# MCU.net
KiCad netlist of a schematic drawn in Altium Designer
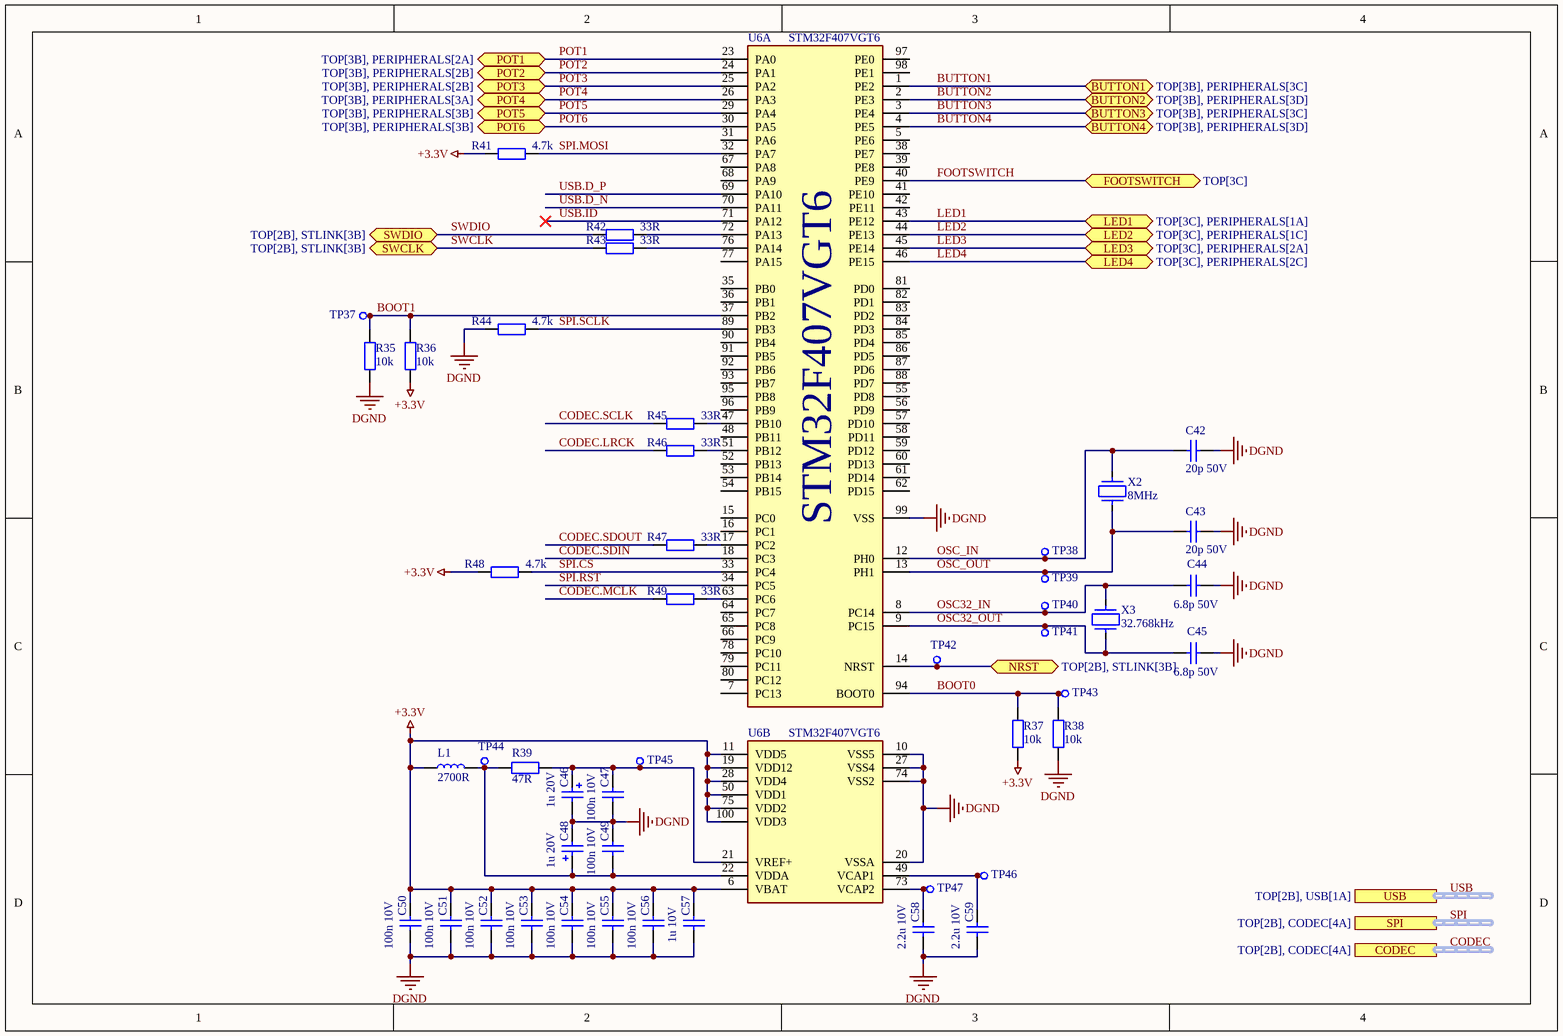
[diagram p0: MCU.SchDoc]

(export (version "E")
  (design (tool "Eeschema 10.0.6"))
  (components
    (comp (ref "C42")
      (value "20p 50V")
      (footprint "FOOTPRINTS:CAPACITOR 0805")
      (description "Capacitor: ceramic; MLCC; 20pF; 50V; C0G (NP0); ±5%; SMD; 0805")
      (fields
        (field (name "MANUFACTURER") "KYOCERA AVX")
        (field (name "MANUFACTURER PART NUMBER") "08055A200JAT2A")
      )
      (libsource (lib "SYMBOLS") (part "Capacitor 20p 50V ±5% NP0 0805"))
    )
    (comp (ref "C43")
      (value "20p 50V")
      (footprint "FOOTPRINTS:CAPACITOR 0805")
      (description "Capacitor: ceramic; MLCC; 20pF; 50V; C0G (NP0); ±5%; SMD; 0805")
      (fields
        (field (name "MANUFACTURER") "KYOCERA AVX")
        (field (name "MANUFACTURER PART NUMBER") "08055A200JAT2A")
      )
      (libsource (lib "SYMBOLS") (part "Capacitor 20p 50V ±5% NP0 0805"))
    )
    (comp (ref "C44")
      (value "6.8p 50V")
      (footprint "FOOTPRINTS:CAPACITOR 0805")
      (description "Capacitor: ceramic; MLCC; 6.8pF; 50V; C0G (NP0); ±0.25pF; SMD; 0805")
      (fields
        (field (name "MANUFACTURER") "YAGEO")
        (field (name "MANUFACTURER PART NUMBER") "CC0805CRNPO96R8")
      )
      (libsource (lib "SYMBOLS") (part "Capacitor 6.8p 50V ±0.25pF NP0 0805"))
    )
    (comp (ref "C45")
      (value "6.8p 50V")
      (footprint "FOOTPRINTS:CAPACITOR 0805")
      (description "Capacitor: ceramic; MLCC; 6.8pF; 50V; C0G (NP0); ±0.25pF; SMD; 0805")
      (fields
        (field (name "MANUFACTURER") "YAGEO")
        (field (name "MANUFACTURER PART NUMBER") "CC0805CRNPO96R8")
      )
      (libsource (lib "SYMBOLS") (part "Capacitor 6.8p 50V ±0.25pF NP0 0805"))
    )
    (comp (ref "C46")
      (value "1u 20V")
      (footprint "FOOTPRINTS:CAPACITOR 1206")
      (description "Capacitor: tantalum; 1uF; 20VDC; SMD; A; 1206; ±10%; -55÷125°C; T491")
      (fields
        (field (name "MANUFACTURER") "KEMET")
        (field (name "MANUFACTURER PART NUMBER") "T491A105K020AT")
      )
      (libsource (lib "SYMBOLS") (part "Capacitor 1u 20V 20% Tantalum 1206"))
    )
    (comp (ref "C47")
      (value "100n 10V")
      (footprint "FOOTPRINTS:CAPACITOR 0805")
      (description "Capacitor: ceramic; MLCC; 100nF; 100V; X7R; ±10%; SMD; 0805")
      (fields
        (field (name "MANUFACTURER") "YAGEO")
        (field (name "MANUFACTURER PART NUMBER") "CC0805KKX7R0BB104")
      )
      (libsource (lib "SYMBOLS") (part "Capacitor 100n 100V 10% X7R 0805"))
    )
    (comp (ref "C48")
      (value "1u 20V")
      (footprint "FOOTPRINTS:CAPACITOR 1206")
      (description "Capacitor: tantalum; 1uF; 20VDC; SMD; A; 1206; ±10%; -55÷125°C; T491")
      (fields
        (field (name "MANUFACTURER") "KEMET")
        (field (name "MANUFACTURER PART NUMBER") "T491A105K020AT")
      )
      (libsource (lib "SYMBOLS") (part "Capacitor 1u 20V 20% Tantalum 1206"))
    )
    (comp (ref "C49")
      (value "100n 10V")
      (footprint "FOOTPRINTS:CAPACITOR 0805")
      (description "Capacitor: ceramic; MLCC; 100nF; 100V; X7R; ±10%; SMD; 0805")
      (fields
        (field (name "MANUFACTURER") "YAGEO")
        (field (name "MANUFACTURER PART NUMBER") "CC0805KKX7R0BB104")
      )
      (libsource (lib "SYMBOLS") (part "Capacitor 100n 100V 10% X7R 0805"))
    )
    (comp (ref "C50")
      (value "100n 10V")
      (footprint "FOOTPRINTS:CAPACITOR 0805")
      (description "Capacitor: ceramic; MLCC; 100nF; 100V; X7R; ±10%; SMD; 0805")
      (fields
        (field (name "MANUFACTURER") "YAGEO")
        (field (name "MANUFACTURER PART NUMBER") "CC0805KKX7R0BB104")
      )
      (libsource (lib "SYMBOLS") (part "Capacitor 100n 100V 10% X7R 0805"))
    )
    (comp (ref "C51")
      (value "100n 10V")
      (footprint "FOOTPRINTS:CAPACITOR 0805")
      (description "Capacitor: ceramic; MLCC; 100nF; 100V; X7R; ±10%; SMD; 0805")
      (fields
        (field (name "MANUFACTURER") "YAGEO")
        (field (name "MANUFACTURER PART NUMBER") "CC0805KKX7R0BB104")
      )
      (libsource (lib "SYMBOLS") (part "Capacitor 100n 100V 10% X7R 0805"))
    )
    (comp (ref "C52")
      (value "100n 10V")
      (footprint "FOOTPRINTS:CAPACITOR 0805")
      (description "Capacitor: ceramic; MLCC; 100nF; 100V; X7R; ±10%; SMD; 0805")
      (fields
        (field (name "MANUFACTURER") "YAGEO")
        (field (name "MANUFACTURER PART NUMBER") "CC0805KKX7R0BB104")
      )
      (libsource (lib "SYMBOLS") (part "Capacitor 100n 100V 10% X7R 0805"))
    )
    (comp (ref "C53")
      (value "100n 10V")
      (footprint "FOOTPRINTS:CAPACITOR 0805")
      (description "Capacitor: ceramic; MLCC; 100nF; 100V; X7R; ±10%; SMD; 0805")
      (fields
        (field (name "MANUFACTURER") "YAGEO")
        (field (name "MANUFACTURER PART NUMBER") "CC0805KKX7R0BB104")
      )
      (libsource (lib "SYMBOLS") (part "Capacitor 100n 100V 10% X7R 0805"))
    )
    (comp (ref "C54")
      (value "100n 10V")
      (footprint "FOOTPRINTS:CAPACITOR 0805")
      (description "Capacitor: ceramic; MLCC; 100nF; 100V; X7R; ±10%; SMD; 0805")
      (fields
        (field (name "MANUFACTURER") "YAGEO")
        (field (name "MANUFACTURER PART NUMBER") "CC0805KKX7R0BB104")
      )
      (libsource (lib "SYMBOLS") (part "Capacitor 100n 100V 10% X7R 0805"))
    )
    (comp (ref "C55")
      (value "100n 10V")
      (footprint "FOOTPRINTS:CAPACITOR 0805")
      (description "Capacitor: ceramic; MLCC; 100nF; 100V; X7R; ±10%; SMD; 0805")
      (fields
        (field (name "MANUFACTURER") "YAGEO")
        (field (name "MANUFACTURER PART NUMBER") "CC0805KKX7R0BB104")
      )
      (libsource (lib "SYMBOLS") (part "Capacitor 100n 100V 10% X7R 0805"))
    )
    (comp (ref "C56")
      (value "100n 10V")
      (footprint "FOOTPRINTS:CAPACITOR 0805")
      (description "Capacitor: ceramic; MLCC; 100nF; 100V; X7R; ±10%; SMD; 0805")
      (fields
        (field (name "MANUFACTURER") "YAGEO")
        (field (name "MANUFACTURER PART NUMBER") "CC0805KKX7R0BB104")
      )
      (libsource (lib "SYMBOLS") (part "Capacitor 100n 100V 10% X7R 0805"))
    )
    (comp (ref "C57")
      (value "1u 10V")
      (footprint "FOOTPRINTS:CAPACITOR 0805")
      (description "Capacitor: ceramic; MLCC; 1uF; 10V; X7R; ±10%; SMD; 0805")
      (fields
        (field (name "MANUFACTURER") "YAGEO")
        (field (name "MANUFACTURER PART NUMBER") "CC0805KKX7R6BB105")
      )
      (libsource (lib "SYMBOLS") (part "Capacitor 1u 10V 10% X7R 0805"))
    )
    (comp (ref "C58")
      (value "2.2u 10V")
      (footprint "FOOTPRINTS:CAPACITOR 0805")
      (description "Multilayer Ceramic Capacitors MLCC - SMD/SMT 0603 16VDC 1uF 10% X7R")
      (fields
        (field (name "MANUFACTURER") "YAGEO")
        (field (name "MANUFACTURER PART NUMBER") "CC0805KKX7R6BB225")
      )
      (libsource (lib "SYMBOLS") (part "Capacitor 2.2u 10V 10% X7R 0805"))
    )
    (comp (ref "C59")
      (value "2.2u 10V")
      (footprint "FOOTPRINTS:CAPACITOR 0805")
      (description "Multilayer Ceramic Capacitors MLCC - SMD/SMT 0603 16VDC 1uF 10% X7R")
      (fields
        (field (name "MANUFACTURER") "YAGEO")
        (field (name "MANUFACTURER PART NUMBER") "CC0805KKX7R6BB225")
      )
      (libsource (lib "SYMBOLS") (part "Capacitor 2.2u 10V 10% X7R 0805"))
    )
    (comp (ref "L1")
      (value "2700R")
      (footprint "FOOTPRINTS:FERRITE 0805")
      (description "Ferrite: bead; 2700Ω; SMD; 200mA; 0805; -55÷125°C")
      (fields
        (field (name "MANUFACTURER") "MURATA")
        (field (name "MANUFACTURER PART NUMBER") "BLM21BD272SN1L")
      )
      (libsource (lib "SYMBOLS") (part "Inductor Ferrite Bead 2700Ω 0805 0.2A"))
    )
    (comp (ref "R35")
      (value "10k")
      (footprint "FOOTPRINTS:RESISTOR 0805")
      (description "Resistor: thick film; SMD; 0805; 10kΩ; 0.125W; ±1%; -55÷155°C")
      (fields
        (field (name "MANUFACTURER") "Yageo")
        (field (name "MANUFACTURER PART NUMBER") "RC0805FR-0710K")
      )
      (libsource (lib "SYMBOLS") (part "Resistor 10k 1% 1/8W 0805"))
    )
    (comp (ref "R36")
      (value "10k")
      (footprint "FOOTPRINTS:RESISTOR 0805")
      (description "Resistor: thick film; SMD; 0805; 10kΩ; 0.125W; ±1%; -55÷155°C")
      (fields
        (field (name "MANUFACTURER") "Yageo")
        (field (name "MANUFACTURER PART NUMBER") "RC0805FR-0710K")
      )
      (libsource (lib "SYMBOLS") (part "Resistor 10k 1% 1/8W 0805"))
    )
    (comp (ref "R37")
      (value "10k")
      (footprint "FOOTPRINTS:RESISTOR 0805")
      (description "Resistor: thick film; SMD; 0805; 10kΩ; 0.125W; ±1%; -55÷155°C")
      (fields
        (field (name "MANUFACTURER") "Yageo")
        (field (name "MANUFACTURER PART NUMBER") "RC0805FR-0710K")
      )
      (libsource (lib "") (part "Resistor 10k 1% 1/8W 0805_1"))
    )
    (comp (ref "R38")
      (value "10k")
      (footprint "FOOTPRINTS:RESISTOR 0805")
      (description "Resistor: thick film; SMD; 0805; 10kΩ; 0.125W; ±1%; -55÷155°C")
      (fields
        (field (name "MANUFACTURER") "Yageo")
        (field (name "MANUFACTURER PART NUMBER") "RC0805FR-0710K")
      )
      (libsource (lib "") (part "Resistor 10k 1% 1/8W 0805_1"))
    )
    (comp (ref "R39")
      (value "47R")
      (footprint "FOOTPRINTS:RESISTOR 0805")
      (description "Resistor: thick film; SMD; 0805; 47Ω; 0.125W; ±1%; -55÷155°C")
      (fields
        (field (name "MANUFACTURER") "Yageo")
        (field (name "MANUFACTURER PART NUMBER") "RC0805FR-0747R")
      )
      (libsource (lib "SYMBOLS") (part "Resistor 47R 1% 1/8W 0805"))
    )
    (comp (ref "R41")
      (value "4.7k")
      (footprint "FOOTPRINTS:RESISTOR 0805")
      (description "Resistor: thick film; SMD; 0805; 4.7kΩ; 0.125W; ±1%; -55÷155°C")
      (fields
        (field (name "MANUFACTURER") "Yageo")
        (field (name "MANUFACTURER PART NUMBER") "RC0805FR-074K7")
      )
      (libsource (lib "SYMBOLS") (part "Resistor 4.7k 1% 1/8W 0805"))
    )
    (comp (ref "R42")
      (value "33R")
      (footprint "FOOTPRINTS:RESISTOR 0805")
      (description "Resistor: thick film; SMD; 0805; 33Ω; 0.125W; ±1%; -55÷155°C")
      (fields
        (field (name "MANUFACTURER") "Yageo")
        (field (name "MANUFACTURER PART NUMBER") "RC0805FR-0733R")
      )
      (libsource (lib "SYMBOLS") (part "Resistor 33R 1% 1/8W 0805"))
    )
    (comp (ref "R43")
      (value "33R")
      (footprint "FOOTPRINTS:RESISTOR 0805")
      (description "Resistor: thick film; SMD; 0805; 33Ω; 0.125W; ±1%; -55÷155°C")
      (fields
        (field (name "MANUFACTURER") "Yageo")
        (field (name "MANUFACTURER PART NUMBER") "RC0805FR-0733R")
      )
      (libsource (lib "SYMBOLS") (part "Resistor 33R 1% 1/8W 0805"))
    )
    (comp (ref "R44")
      (value "4.7k")
      (footprint "FOOTPRINTS:RESISTOR 0805")
      (description "Resistor: thick film; SMD; 0805; 4.7kΩ; 0.125W; ±1%; -55÷155°C")
      (fields
        (field (name "MANUFACTURER") "Yageo")
        (field (name "MANUFACTURER PART NUMBER") "RC0805FR-074K7")
      )
      (libsource (lib "SYMBOLS") (part "Resistor 4.7k 1% 1/8W 0805"))
    )
    (comp (ref "R45")
      (value "33R")
      (footprint "FOOTPRINTS:RESISTOR 0805")
      (description "Resistor: thick film; SMD; 0805; 33Ω; 0.125W; ±1%; -55÷155°C")
      (fields
        (field (name "MANUFACTURER") "Yageo")
        (field (name "MANUFACTURER PART NUMBER") "RC0805FR-0733R")
      )
      (libsource (lib "SYMBOLS") (part "Resistor 33R 1% 1/8W 0805"))
    )
    (comp (ref "R46")
      (value "33R")
      (footprint "FOOTPRINTS:RESISTOR 0805")
      (description "Resistor: thick film; SMD; 0805; 33Ω; 0.125W; ±1%; -55÷155°C")
      (fields
        (field (name "MANUFACTURER") "Yageo")
        (field (name "MANUFACTURER PART NUMBER") "RC0805FR-0733R")
      )
      (libsource (lib "SYMBOLS") (part "Resistor 33R 1% 1/8W 0805"))
    )
    (comp (ref "R47")
      (value "33R")
      (footprint "FOOTPRINTS:RESISTOR 0805")
      (description "Resistor: thick film; SMD; 0805; 33Ω; 0.125W; ±1%; -55÷155°C")
      (fields
        (field (name "MANUFACTURER") "Yageo")
        (field (name "MANUFACTURER PART NUMBER") "RC0805FR-0733R")
      )
      (libsource (lib "SYMBOLS") (part "Resistor 33R 1% 1/8W 0805"))
    )
    (comp (ref "R48")
      (value "4.7k")
      (footprint "FOOTPRINTS:RESISTOR 0805")
      (description "Resistor: thick film; SMD; 0805; 4.7kΩ; 0.125W; ±1%; -55÷155°C")
      (fields
        (field (name "MANUFACTURER") "Yageo")
        (field (name "MANUFACTURER PART NUMBER") "RC0805FR-074K7")
      )
      (libsource (lib "SYMBOLS") (part "Resistor 4.7k 1% 1/8W 0805"))
    )
    (comp (ref "R49")
      (value "33R")
      (footprint "FOOTPRINTS:RESISTOR 0805")
      (description "Resistor: thick film; SMD; 0805; 33Ω; 0.125W; ±1%; -55÷155°C")
      (fields
        (field (name "MANUFACTURER") "Yageo")
        (field (name "MANUFACTURER PART NUMBER") "RC0805FR-0733R")
      )
      (libsource (lib "SYMBOLS") (part "Resistor 33R 1% 1/8W 0805"))
    )
    (comp (ref "TP37")
      (value "1mm")
      (footprint "FOOTPRINTS:TEST POINT 1MM")
      (description "Tesp Point 1mm")
      (libsource (lib "SYMBOLS") (part "Mechanical Test Point 1mm"))
    )
    (comp (ref "TP38")
      (value "1mm")
      (footprint "FOOTPRINTS:TEST POINT 1MM")
      (description "Tesp Point 1mm")
      (libsource (lib "SYMBOLS") (part "Mechanical Test Point 1mm"))
    )
    (comp (ref "TP39")
      (value "1mm")
      (footprint "FOOTPRINTS:TEST POINT 1MM")
      (description "Tesp Point 1mm")
      (libsource (lib "SYMBOLS") (part "Mechanical Test Point 1mm"))
    )
    (comp (ref "TP40")
      (value "1mm")
      (footprint "FOOTPRINTS:TEST POINT 1MM")
      (description "Tesp Point 1mm")
      (libsource (lib "SYMBOLS") (part "Mechanical Test Point 1mm"))
    )
    (comp (ref "TP41")
      (value "1mm")
      (footprint "FOOTPRINTS:TEST POINT 1MM")
      (description "Tesp Point 1mm")
      (libsource (lib "SYMBOLS") (part "Mechanical Test Point 1mm"))
    )
    (comp (ref "TP42")
      (value "1mm")
      (footprint "FOOTPRINTS:TEST POINT 1MM")
      (description "Tesp Point 1mm")
      (libsource (lib "SYMBOLS") (part "Mechanical Test Point 1mm"))
    )
    (comp (ref "TP43")
      (value "1mm")
      (footprint "FOOTPRINTS:TEST POINT 1MM")
      (description "Tesp Point 1mm")
      (libsource (lib "SYMBOLS") (part "Mechanical Test Point 1mm"))
    )
    (comp (ref "TP44")
      (value "1mm")
      (footprint "FOOTPRINTS:TEST POINT 1MM")
      (description "Tesp Point 1mm")
      (libsource (lib "SYMBOLS") (part "Mechanical Test Point 1mm"))
    )
    (comp (ref "TP45")
      (value "1mm")
      (footprint "FOOTPRINTS:TEST POINT 1MM")
      (description "Tesp Point 1mm")
      (libsource (lib "SYMBOLS") (part "Mechanical Test Point 1mm"))
    )
    (comp (ref "TP46")
      (value "1mm")
      (footprint "FOOTPRINTS:TEST POINT 1MM")
      (description "Tesp Point 1mm")
      (libsource (lib "SYMBOLS") (part "Mechanical Test Point 1mm"))
    )
    (comp (ref "TP47")
      (value "1mm")
      (footprint "FOOTPRINTS:TEST POINT 1MM")
      (description "Tesp Point 1mm")
      (libsource (lib "SYMBOLS") (part "Mechanical Test Point 1mm"))
    )
    (comp (ref "U6")
      (value "STM32F407VGT6")
      (footprint "FOOTPRINTS:LQFP-100")
      (description "IC: ARM microcontroller; 168MHz; LQFP100; 1.8÷3.6VDC")
      (fields (field (name "MANUFACTURER") "STMicroelectronics"))
      (libsource (lib "SYMBOLS") (part "IC MCU ARM M4 STM32F407VGT6"))
    )
    (comp (ref "X2")
      (value "8MHz")
      (footprint "FOOTPRINTS:OSCILLATOR 8MHZ SMD")
      (description "Crystals CRYSTAL 8.0000MHZ 20PF SMD")
      (fields
        (field (name "MANUFACTURER") "ABRACON")
        (field (name "MANUFACTURER PART NUMBER") "ABLS-8.000MHZ-20-B-3-H-T")
      )
      (libsource (lib "SYMBOLS") (part "Crystal 8MHz 20p SMD"))
    )
    (comp (ref "X3")
      (value "32.768kHz")
      (footprint "FOOTPRINTS:OSCILLATOR 32.768KHZ SMD")
      (description "Resonator: watch; 32.768kHz; ±20ppm; SMD; 8x3.2x2.38mm")
      (fields
        (field (name "MANUFACTURER") "EPSON")
        (field (name "MANUFACTURER PART NUMBER") "MC306 32.768000KHZ 12.5PF")
      )
      (libsource (lib "SYMBOLS") (part "Crystal 32.768kHz 8x3.2x2.38mm SMD"))
    )
  )
  (nets
    (net (code "4") (name "+3.3V") (class "Default")
      (node (ref "C50") (pin "2") (pinfunction "2_2") (pintype "passive"))
      (node (ref "C51") (pin "2") (pinfunction "2_2") (pintype "passive"))
      (node (ref "C52") (pin "2") (pinfunction "2_2") (pintype "passive"))
      (node (ref "C53") (pin "2") (pinfunction "2_2") (pintype "passive"))
      (node (ref "C54") (pin "2") (pinfunction "2_2") (pintype "passive"))
      (node (ref "C55") (pin "2") (pinfunction "2_2") (pintype "passive"))
      (node (ref "C56") (pin "2") (pinfunction "2_2") (pintype "passive"))
      (node (ref "C57") (pin "2") (pinfunction "2_2") (pintype "passive"))
      (node (ref "L1") (pin "1") (pinfunction "1_1") (pintype "passive"))
      (node (ref "R36") (pin "1") (pinfunction "1_1") (pintype "passive"))
      (node (ref "R37") (pin "1") (pinfunction "1_1") (pintype "passive"))
      (node (ref "R41") (pin "1") (pinfunction "1_1") (pintype "passive"))
      (node (ref "R48") (pin "1") (pinfunction "1_1") (pintype "passive"))
      (node (ref "U6") (pin "100") (pinfunction "VDD3_100") (pintype "passive"))
      (node (ref "U6") (pin "11") (pinfunction "VDD5_11") (pintype "passive"))
      (node (ref "U6") (pin "19") (pinfunction "VDD12_19") (pintype "passive"))
      (node (ref "U6") (pin "28") (pinfunction "VDD4_28") (pintype "passive"))
      (node (ref "U6") (pin "50") (pinfunction "VDD1_50") (pintype "passive"))
      (node (ref "U6") (pin "6") (pinfunction "VBAT_6") (pintype "passive"))
      (node (ref "U6") (pin "75") (pinfunction "VDD2_75") (pintype "passive"))
    )
    (net (code "5") (name "/BOOT0") (class "Default")
      (node (ref "R37") (pin "2") (pinfunction "2_2") (pintype "passive"))
      (node (ref "R38") (pin "2") (pinfunction "2_2") (pintype "passive"))
      (node (ref "TP43") (pin "1") (pinfunction "1_1") (pintype "passive"))
      (node (ref "U6") (pin "94") (pinfunction "BOOT0_94") (pintype "passive"))
    )
    (net (code "6") (name "/BOOT1") (class "Default")
      (node (ref "R35") (pin "2") (pinfunction "2_2") (pintype "passive"))
      (node (ref "R36") (pin "2") (pinfunction "2_2") (pintype "passive"))
      (node (ref "TP37") (pin "1") (pinfunction "1_1") (pintype "passive"))
      (node (ref "U6") (pin "37") (pinfunction "PB2_37") (pintype "passive"))
    )
    (net (code "7") (name "/BUTTON1") (class "Default")
      (node (ref "U6") (pin "1") (pinfunction "PE2_1") (pintype "passive"))
    )
    (net (code "8") (name "/BUTTON2") (class "Default")
      (node (ref "U6") (pin "2") (pinfunction "PE3_2") (pintype "passive"))
    )
    (net (code "9") (name "/BUTTON3") (class "Default")
      (node (ref "U6") (pin "3") (pinfunction "PE4_3") (pintype "passive"))
    )
    (net (code "10") (name "/BUTTON4") (class "Default")
      (node (ref "U6") (pin "4") (pinfunction "PE5_4") (pintype "passive"))
    )
    (net (code "11") (name "/CODEC.LRCK") (class "Default")
      (node (ref "R46") (pin "1") (pinfunction "1_1") (pintype "passive"))
    )
    (net (code "12") (name "/CODEC.MCLK") (class "Default")
      (node (ref "R49") (pin "1") (pinfunction "1_1") (pintype "passive"))
    )
    (net (code "13") (name "/CODEC.SCLK") (class "Default")
      (node (ref "R45") (pin "1") (pinfunction "1_1") (pintype "passive"))
    )
    (net (code "14") (name "/CODEC.SDIN") (class "Default")
      (node (ref "U6") (pin "18") (pinfunction "PC3_18") (pintype "passive"))
    )
    (net (code "15") (name "/CODEC.SDOUT") (class "Default")
      (node (ref "R47") (pin "1") (pinfunction "1_1") (pintype "passive"))
    )
    (net (code "16") (name "/FOOTSWITCH") (class "Default")
      (node (ref "U6") (pin "40") (pinfunction "PE9_40") (pintype "passive"))
    )
    (net (code "17") (name "/LED1") (class "Default")
      (node (ref "U6") (pin "43") (pinfunction "PE12_43") (pintype "passive"))
    )
    (net (code "18") (name "/LED2") (class "Default")
      (node (ref "U6") (pin "44") (pinfunction "PE13_44") (pintype "passive"))
    )
    (net (code "19") (name "/LED3") (class "Default")
      (node (ref "U6") (pin "45") (pinfunction "PE14_45") (pintype "passive"))
    )
    (net (code "20") (name "/LED4") (class "Default")
      (node (ref "U6") (pin "46") (pinfunction "PE15_46") (pintype "passive"))
    )
    (net (code "21") (name "/NRST") (class "Default")
      (node (ref "TP42") (pin "1") (pinfunction "1_1") (pintype "passive"))
      (node (ref "U6") (pin "14") (pinfunction "NRST_14") (pintype "passive"))
    )
    (net (code "22") (name "/OSC32_IN") (class "Default")
      (node (ref "C44") (pin "1") (pinfunction "1_1") (pintype "passive"))
      (node (ref "TP40") (pin "1") (pinfunction "1_1") (pintype "passive"))
      (node (ref "U6") (pin "8") (pinfunction "PC14_8") (pintype "passive"))
      (node (ref "X3") (pin "1") (pinfunction "1_1") (pintype "passive"))
    )
    (net (code "23") (name "/OSC32_OUT") (class "Default")
      (node (ref "C45") (pin "1") (pinfunction "1_1") (pintype "passive"))
      (node (ref "TP41") (pin "1") (pinfunction "1_1") (pintype "passive"))
      (node (ref "U6") (pin "9") (pinfunction "PC15_9") (pintype "passive"))
      (node (ref "X3") (pin "4") (pinfunction "4_4") (pintype "passive"))
    )
    (net (code "24") (name "/OSC_IN") (class "Default")
      (node (ref "C42") (pin "1") (pinfunction "1_1") (pintype "passive"))
      (node (ref "TP38") (pin "1") (pinfunction "1_1") (pintype "passive"))
      (node (ref "U6") (pin "12") (pinfunction "PH0_12") (pintype "passive"))
      (node (ref "X2") (pin "2") (pinfunction "2_2") (pintype "passive"))
    )
    (net (code "25") (name "/OSC_OUT") (class "Default")
      (node (ref "C43") (pin "1") (pinfunction "1_1") (pintype "passive"))
      (node (ref "TP39") (pin "1") (pinfunction "1_1") (pintype "passive"))
      (node (ref "U6") (pin "13") (pinfunction "PH1_13") (pintype "passive"))
      (node (ref "X2") (pin "1") (pinfunction "1_1") (pintype "passive"))
    )
    (net (code "26") (name "/POT1") (class "Default")
      (node (ref "U6") (pin "23") (pinfunction "PA0_23") (pintype "passive"))
    )
    (net (code "27") (name "/POT2") (class "Default")
      (node (ref "U6") (pin "24") (pinfunction "PA1_24") (pintype "passive"))
    )
    (net (code "28") (name "/POT3") (class "Default")
      (node (ref "U6") (pin "25") (pinfunction "PA2_25") (pintype "passive"))
    )
    (net (code "29") (name "/POT4") (class "Default")
      (node (ref "U6") (pin "26") (pinfunction "PA3_26") (pintype "passive"))
    )
    (net (code "30") (name "/POT5") (class "Default")
      (node (ref "U6") (pin "29") (pinfunction "PA4_29") (pintype "passive"))
    )
    (net (code "31") (name "/POT6") (class "Default")
      (node (ref "U6") (pin "30") (pinfunction "PA5_30") (pintype "passive"))
    )
    (net (code "32") (name "/SPI.MOSI") (class "Default")
      (node (ref "R41") (pin "2") (pinfunction "2_2") (pintype "passive"))
      (node (ref "U6") (pin "32") (pinfunction "PA7_32") (pintype "passive"))
    )
    (net (code "33") (name "/SPI.SCLK") (class "Default")
      (node (ref "R44") (pin "2") (pinfunction "2_2") (pintype "passive"))
      (node (ref "U6") (pin "89") (pinfunction "PB3_89") (pintype "passive"))
    )
    (net (code "34") (name "/SPI.~{CS}") (class "Default")
      (node (ref "R48") (pin "2") (pinfunction "2_2") (pintype "passive"))
      (node (ref "U6") (pin "33") (pinfunction "PC4_33") (pintype "passive"))
    )
    (net (code "35") (name "/SPI.~{RST}") (class "Default")
      (node (ref "U6") (pin "34") (pinfunction "PC5_34") (pintype "passive"))
    )
    (net (code "36") (name "/SWCLK") (class "Default")
      (node (ref "R43") (pin "1") (pinfunction "1_1") (pintype "passive"))
    )
    (net (code "37") (name "/SWDIO") (class "Default")
      (node (ref "R42") (pin "1") (pinfunction "1_1") (pintype "passive"))
    )
    (net (code "38") (name "/USB.D_N") (class "Default")
      (node (ref "U6") (pin "70") (pinfunction "PA11_70") (pintype "passive"))
    )
    (net (code "39") (name "/USB.D_P") (class "Default")
      (node (ref "U6") (pin "69") (pinfunction "PA10_69") (pintype "passive"))
    )
    (net (code "40") (name "/USB.ID") (class "Default")
      (node (ref "U6") (pin "71") (pinfunction "PA12_71") (pintype "passive+no_connect"))
    )
    (net (code "44") (name "DGND") (class "Default")
      (node (ref "C42") (pin "2") (pinfunction "2_2") (pintype "passive"))
      (node (ref "C43") (pin "2") (pinfunction "2_2") (pintype "passive"))
      (node (ref "C44") (pin "2") (pinfunction "2_2") (pintype "passive"))
      (node (ref "C45") (pin "2") (pinfunction "2_2") (pintype "passive"))
      (node (ref "C46") (pin "2") (pinfunction "2_2") (pintype "passive"))
      (node (ref "C47") (pin "1") (pinfunction "1_1") (pintype "passive"))
      (node (ref "C48") (pin "2") (pinfunction "2_2") (pintype "passive"))
      (node (ref "C49") (pin "2") (pinfunction "2_2") (pintype "passive"))
      (node (ref "C50") (pin "1") (pinfunction "1_1") (pintype "passive"))
      (node (ref "C51") (pin "1") (pinfunction "1_1") (pintype "passive"))
      (node (ref "C52") (pin "1") (pinfunction "1_1") (pintype "passive"))
      (node (ref "C53") (pin "1") (pinfunction "1_1") (pintype "passive"))
      (node (ref "C54") (pin "1") (pinfunction "1_1") (pintype "passive"))
      (node (ref "C55") (pin "1") (pinfunction "1_1") (pintype "passive"))
      (node (ref "C56") (pin "1") (pinfunction "1_1") (pintype "passive"))
      (node (ref "C57") (pin "1") (pinfunction "1_1") (pintype "passive"))
      (node (ref "C58") (pin "1") (pinfunction "1_1") (pintype "passive"))
      (node (ref "C59") (pin "1") (pinfunction "1_1") (pintype "passive"))
      (node (ref "R35") (pin "1") (pinfunction "1_1") (pintype "passive"))
      (node (ref "R38") (pin "1") (pinfunction "1_1") (pintype "passive"))
      (node (ref "R44") (pin "1") (pinfunction "1_1") (pintype "passive"))
      (node (ref "U6") (pin "10") (pinfunction "VSS5_10") (pintype "passive"))
      (node (ref "U6") (pin "20") (pinfunction "VSSA_20") (pintype "passive"))
      (node (ref "U6") (pin "27") (pinfunction "VSS4_27") (pintype "passive"))
      (node (ref "U6") (pin "74") (pinfunction "VSS2_74") (pintype "passive"))
      (node (ref "U6") (pin "99") (pinfunction "VSS_99") (pintype "passive"))
    )
    (net (code "45") (name "Net-(U6A-PA13)") (class "Default")
      (node (ref "R42") (pin "2") (pinfunction "2_2") (pintype "passive"))
      (node (ref "U6") (pin "72") (pinfunction "PA13_72") (pintype "passive"))
    )
    (net (code "46") (name "Net-(U6A-PA14)") (class "Default")
      (node (ref "R43") (pin "2") (pinfunction "2_2") (pintype "passive"))
      (node (ref "U6") (pin "76") (pinfunction "PA14_76") (pintype "passive"))
    )
    (net (code "47") (name "Net-(U6A-PB10)") (class "Default")
      (node (ref "R45") (pin "2") (pinfunction "2_2") (pintype "passive"))
      (node (ref "U6") (pin "47") (pinfunction "PB10_47") (pintype "passive"))
    )
    (net (code "48") (name "Net-(U6A-PB12)") (class "Default")
      (node (ref "R46") (pin "2") (pinfunction "2_2") (pintype "passive"))
      (node (ref "U6") (pin "51") (pinfunction "PB12_51") (pintype "passive"))
    )
    (net (code "49") (name "Net-(U6A-PC2)") (class "Default")
      (node (ref "R47") (pin "2") (pinfunction "2_2") (pintype "passive"))
      (node (ref "U6") (pin "17") (pinfunction "PC2_17") (pintype "passive"))
    )
    (net (code "50") (name "Net-(U6A-PC6)") (class "Default")
      (node (ref "R49") (pin "2") (pinfunction "2_2") (pintype "passive"))
      (node (ref "U6") (pin "63") (pinfunction "PC6_63") (pintype "passive"))
    )
    (net (code "51") (name "Net-(U6B-VCAP1)") (class "Default")
      (node (ref "C59") (pin "2") (pinfunction "2_2") (pintype "passive"))
      (node (ref "TP46") (pin "1") (pinfunction "1_1") (pintype "passive"))
      (node (ref "U6") (pin "49") (pinfunction "VCAP1_49") (pintype "passive"))
    )
    (net (code "52") (name "Net-(U6B-VCAP2)") (class "Default")
      (node (ref "C58") (pin "2") (pinfunction "2_2") (pintype "passive"))
      (node (ref "TP47") (pin "1") (pinfunction "1_1") (pintype "passive"))
      (node (ref "U6") (pin "73") (pinfunction "VCAP2_73") (pintype "passive"))
    )
    (net (code "53") (name "Net-(U6B-VDDA)") (class "Default")
      (node (ref "C48") (pin "1") (pinfunction "1_1") (pintype "passive"))
      (node (ref "C49") (pin "1") (pinfunction "1_1") (pintype "passive"))
      (node (ref "L1") (pin "2") (pinfunction "2_2") (pintype "passive"))
      (node (ref "R39") (pin "1") (pinfunction "1_1") (pintype "passive"))
      (node (ref "TP44") (pin "1") (pinfunction "1_1") (pintype "passive"))
      (node (ref "U6") (pin "22") (pinfunction "VDDA_22") (pintype "passive"))
    )
    (net (code "54") (name "Net-(U6B-VREF+)") (class "Default")
      (node (ref "C46") (pin "1") (pinfunction "1_1") (pintype "passive"))
      (node (ref "C47") (pin "2") (pinfunction "2_2") (pintype "passive"))
      (node (ref "R39") (pin "2") (pinfunction "2_2") (pintype "passive"))
      (node (ref "TP45") (pin "1") (pinfunction "1_1") (pintype "passive"))
      (node (ref "U6") (pin "21") (pinfunction "VREF+_21") (pintype "passive"))
    )
    (net (code "55") (name "unconnected-(U6A-PA6-Pad31)") (class "Default")
      (node (ref "U6") (pin "31") (pinfunction "PA6_31") (pintype "passive"))
    )
    (net (code "56") (name "unconnected-(U6A-PA8-Pad67)") (class "Default")
      (node (ref "U6") (pin "67") (pinfunction "PA8_67") (pintype "passive"))
    )
    (net (code "57") (name "unconnected-(U6A-PA9-Pad68)") (class "Default")
      (node (ref "U6") (pin "68") (pinfunction "PA9_68") (pintype "passive"))
    )
    (net (code "58") (name "unconnected-(U6A-PA15-Pad77)") (class "Default")
      (node (ref "U6") (pin "77") (pinfunction "PA15_77") (pintype "passive"))
    )
    (net (code "59") (name "unconnected-(U6A-PB0-Pad35)") (class "Default")
      (node (ref "U6") (pin "35") (pinfunction "PB0_35") (pintype "passive"))
    )
    (net (code "60") (name "unconnected-(U6A-PB1-Pad36)") (class "Default")
      (node (ref "U6") (pin "36") (pinfunction "PB1_36") (pintype "passive"))
    )
    (net (code "61") (name "unconnected-(U6A-PB4-Pad90)") (class "Default")
      (node (ref "U6") (pin "90") (pinfunction "PB4_90") (pintype "passive"))
    )
    (net (code "62") (name "unconnected-(U6A-PB5-Pad91)") (class "Default")
      (node (ref "U6") (pin "91") (pinfunction "PB5_91") (pintype "passive"))
    )
    (net (code "63") (name "unconnected-(U6A-PB6-Pad92)") (class "Default")
      (node (ref "U6") (pin "92") (pinfunction "PB6_92") (pintype "passive"))
    )
    (net (code "64") (name "unconnected-(U6A-PB7-Pad93)") (class "Default")
      (node (ref "U6") (pin "93") (pinfunction "PB7_93") (pintype "passive"))
    )
    (net (code "65") (name "unconnected-(U6A-PB8-Pad95)") (class "Default")
      (node (ref "U6") (pin "95") (pinfunction "PB8_95") (pintype "passive"))
    )
    (net (code "66") (name "unconnected-(U6A-PB9-Pad96)") (class "Default")
      (node (ref "U6") (pin "96") (pinfunction "PB9_96") (pintype "passive"))
    )
    (net (code "67") (name "unconnected-(U6A-PB11-Pad48)") (class "Default")
      (node (ref "U6") (pin "48") (pinfunction "PB11_48") (pintype "passive"))
    )
    (net (code "68") (name "unconnected-(U6A-PB13-Pad52)") (class "Default")
      (node (ref "U6") (pin "52") (pinfunction "PB13_52") (pintype "passive"))
    )
    (net (code "69") (name "unconnected-(U6A-PB14-Pad53)") (class "Default")
      (node (ref "U6") (pin "53") (pinfunction "PB14_53") (pintype "passive"))
    )
    (net (code "70") (name "unconnected-(U6A-PB15-Pad54)") (class "Default")
      (node (ref "U6") (pin "54") (pinfunction "PB15_54") (pintype "passive"))
    )
    (net (code "71") (name "unconnected-(U6A-PC0-Pad15)") (class "Default")
      (node (ref "U6") (pin "15") (pinfunction "PC0_15") (pintype "passive"))
    )
    (net (code "72") (name "unconnected-(U6A-PC1-Pad16)") (class "Default")
      (node (ref "U6") (pin "16") (pinfunction "PC1_16") (pintype "passive"))
    )
    (net (code "73") (name "unconnected-(U6A-PC7-Pad64)") (class "Default")
      (node (ref "U6") (pin "64") (pinfunction "PC7_64") (pintype "passive"))
    )
    (net (code "74") (name "unconnected-(U6A-PC8-Pad65)") (class "Default")
      (node (ref "U6") (pin "65") (pinfunction "PC8_65") (pintype "passive"))
    )
    (net (code "75") (name "unconnected-(U6A-PC9-Pad66)") (class "Default")
      (node (ref "U6") (pin "66") (pinfunction "PC9_66") (pintype "passive"))
    )
    (net (code "76") (name "unconnected-(U6A-PC10-Pad78)") (class "Default")
      (node (ref "U6") (pin "78") (pinfunction "PC10_78") (pintype "passive"))
    )
    (net (code "77") (name "unconnected-(U6A-PC11-Pad79)") (class "Default")
      (node (ref "U6") (pin "79") (pinfunction "PC11_79") (pintype "passive"))
    )
    (net (code "78") (name "unconnected-(U6A-PC12-Pad80)") (class "Default")
      (node (ref "U6") (pin "80") (pinfunction "PC12_80") (pintype "passive"))
    )
    (net (code "79") (name "unconnected-(U6A-PC13-Pad7)") (class "Default")
      (node (ref "U6") (pin "7") (pinfunction "PC13_7") (pintype "passive"))
    )
    (net (code "80") (name "unconnected-(U6A-PD0-Pad81)") (class "Default")
      (node (ref "U6") (pin "81") (pinfunction "PD0_81") (pintype "passive"))
    )
    (net (code "81") (name "unconnected-(U6A-PD1-Pad82)") (class "Default")
      (node (ref "U6") (pin "82") (pinfunction "PD1_82") (pintype "passive"))
    )
    (net (code "82") (name "unconnected-(U6A-PD2-Pad83)") (class "Default")
      (node (ref "U6") (pin "83") (pinfunction "PD2_83") (pintype "passive"))
    )
    (net (code "83") (name "unconnected-(U6A-PD3-Pad84)") (class "Default")
      (node (ref "U6") (pin "84") (pinfunction "PD3_84") (pintype "passive"))
    )
    (net (code "84") (name "unconnected-(U6A-PD4-Pad85)") (class "Default")
      (node (ref "U6") (pin "85") (pinfunction "PD4_85") (pintype "passive"))
    )
    (net (code "85") (name "unconnected-(U6A-PD5-Pad86)") (class "Default")
      (node (ref "U6") (pin "86") (pinfunction "PD5_86") (pintype "passive"))
    )
    (net (code "86") (name "unconnected-(U6A-PD6-Pad87)") (class "Default")
      (node (ref "U6") (pin "87") (pinfunction "PD6_87") (pintype "passive"))
    )
    (net (code "87") (name "unconnected-(U6A-PD7-Pad88)") (class "Default")
      (node (ref "U6") (pin "88") (pinfunction "PD7_88") (pintype "passive"))
    )
    (net (code "88") (name "unconnected-(U6A-PD8-Pad55)") (class "Default")
      (node (ref "U6") (pin "55") (pinfunction "PD8_55") (pintype "passive"))
    )
    (net (code "89") (name "unconnected-(U6A-PD9-Pad56)") (class "Default")
      (node (ref "U6") (pin "56") (pinfunction "PD9_56") (pintype "passive"))
    )
    (net (code "90") (name "unconnected-(U6A-PD10-Pad57)") (class "Default")
      (node (ref "U6") (pin "57") (pinfunction "PD10_57") (pintype "passive"))
    )
    (net (code "91") (name "unconnected-(U6A-PD11-Pad58)") (class "Default")
      (node (ref "U6") (pin "58") (pinfunction "PD11_58") (pintype "passive"))
    )
    (net (code "92") (name "unconnected-(U6A-PD12-Pad59)") (class "Default")
      (node (ref "U6") (pin "59") (pinfunction "PD12_59") (pintype "passive"))
    )
    (net (code "93") (name "unconnected-(U6A-PD13-Pad60)") (class "Default")
      (node (ref "U6") (pin "60") (pinfunction "PD13_60") (pintype "passive"))
    )
    (net (code "94") (name "unconnected-(U6A-PD14-Pad61)") (class "Default")
      (node (ref "U6") (pin "61") (pinfunction "PD14_61") (pintype "passive"))
    )
    (net (code "95") (name "unconnected-(U6A-PD15-Pad62)") (class "Default")
      (node (ref "U6") (pin "62") (pinfunction "PD15_62") (pintype "passive"))
    )
    (net (code "96") (name "unconnected-(U6A-PE0-Pad97)") (class "Default")
      (node (ref "U6") (pin "97") (pinfunction "PE0_97") (pintype "passive"))
    )
    (net (code "97") (name "unconnected-(U6A-PE1-Pad98)") (class "Default")
      (node (ref "U6") (pin "98") (pinfunction "PE1_98") (pintype "passive"))
    )
    (net (code "98") (name "unconnected-(U6A-PE6-Pad5)") (class "Default")
      (node (ref "U6") (pin "5") (pinfunction "PE6_5") (pintype "passive"))
    )
    (net (code "99") (name "unconnected-(U6A-PE7-Pad38)") (class "Default")
      (node (ref "U6") (pin "38") (pinfunction "PE7_38") (pintype "passive"))
    )
    (net (code "100") (name "unconnected-(U6A-PE8-Pad39)") (class "Default")
      (node (ref "U6") (pin "39") (pinfunction "PE8_39") (pintype "passive"))
    )
    (net (code "101") (name "unconnected-(U6A-PE10-Pad41)") (class "Default")
      (node (ref "U6") (pin "41") (pinfunction "PE10_41") (pintype "passive"))
    )
    (net (code "102") (name "unconnected-(U6A-PE11-Pad42)") (class "Default")
      (node (ref "U6") (pin "42") (pinfunction "PE11_42") (pintype "passive"))
    )
  )
)
